# Battery_Monitoring_V2.net
KiCad netlist of a schematic drawn in EAGLE
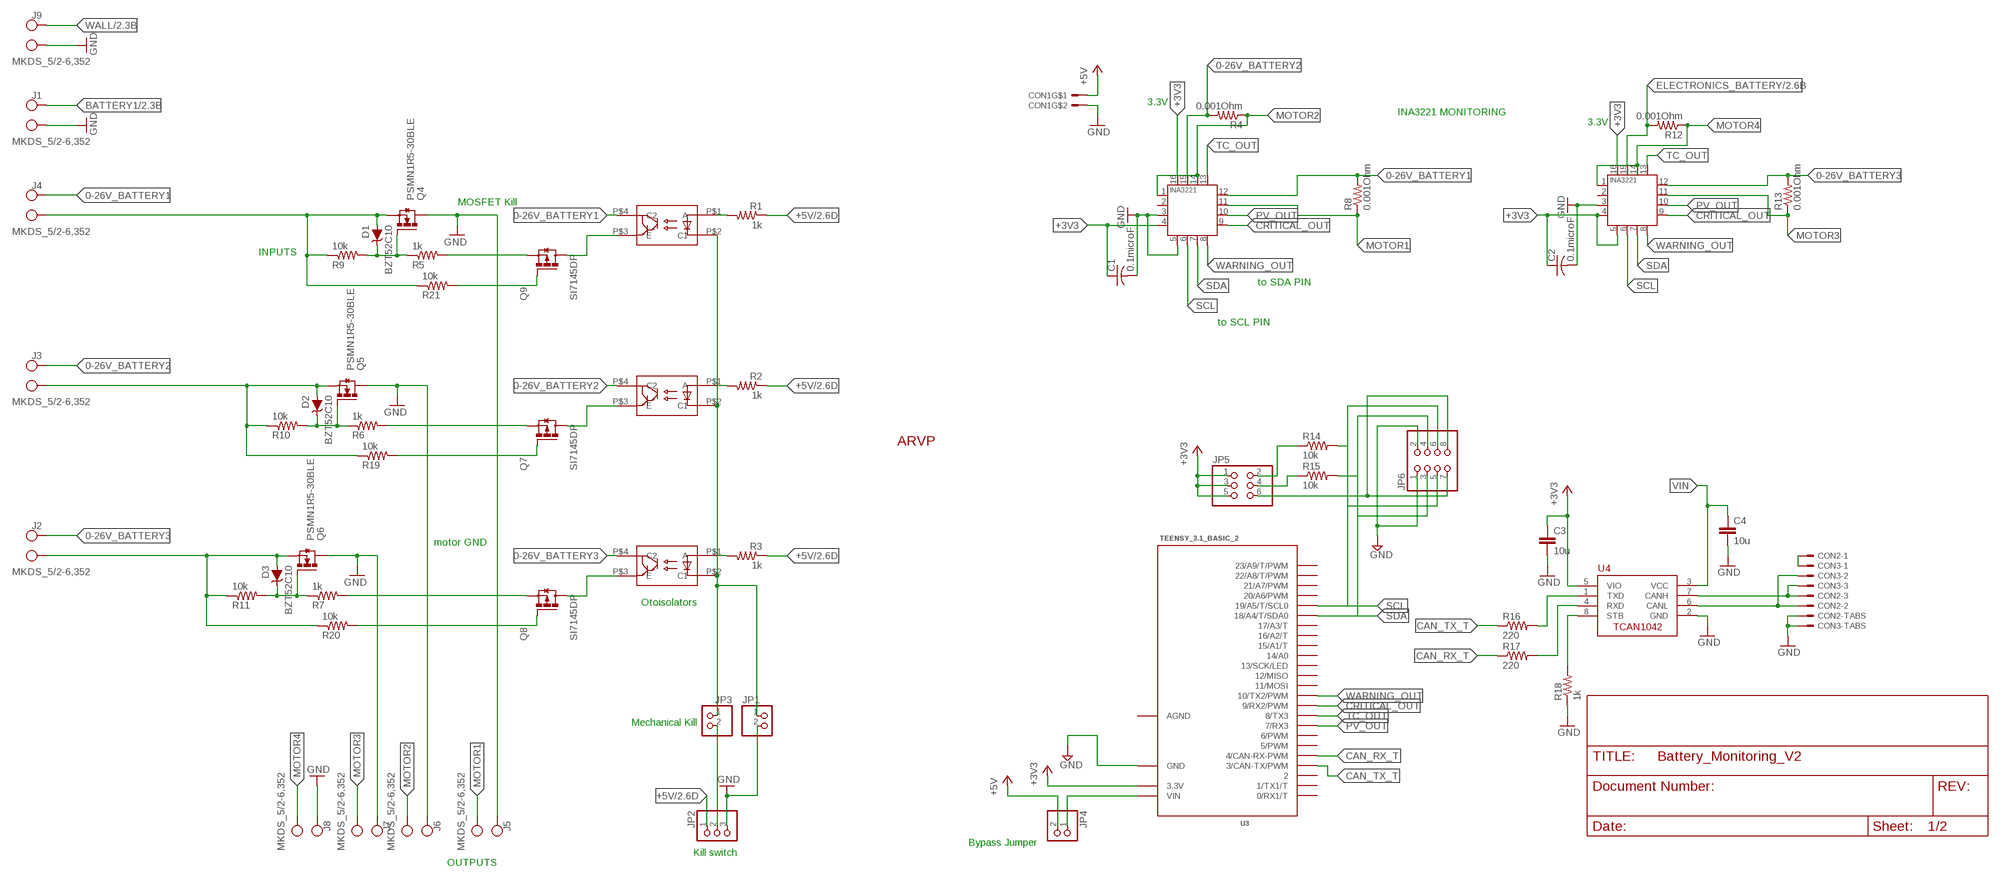
[diagram p0: schematic, sheet 1]
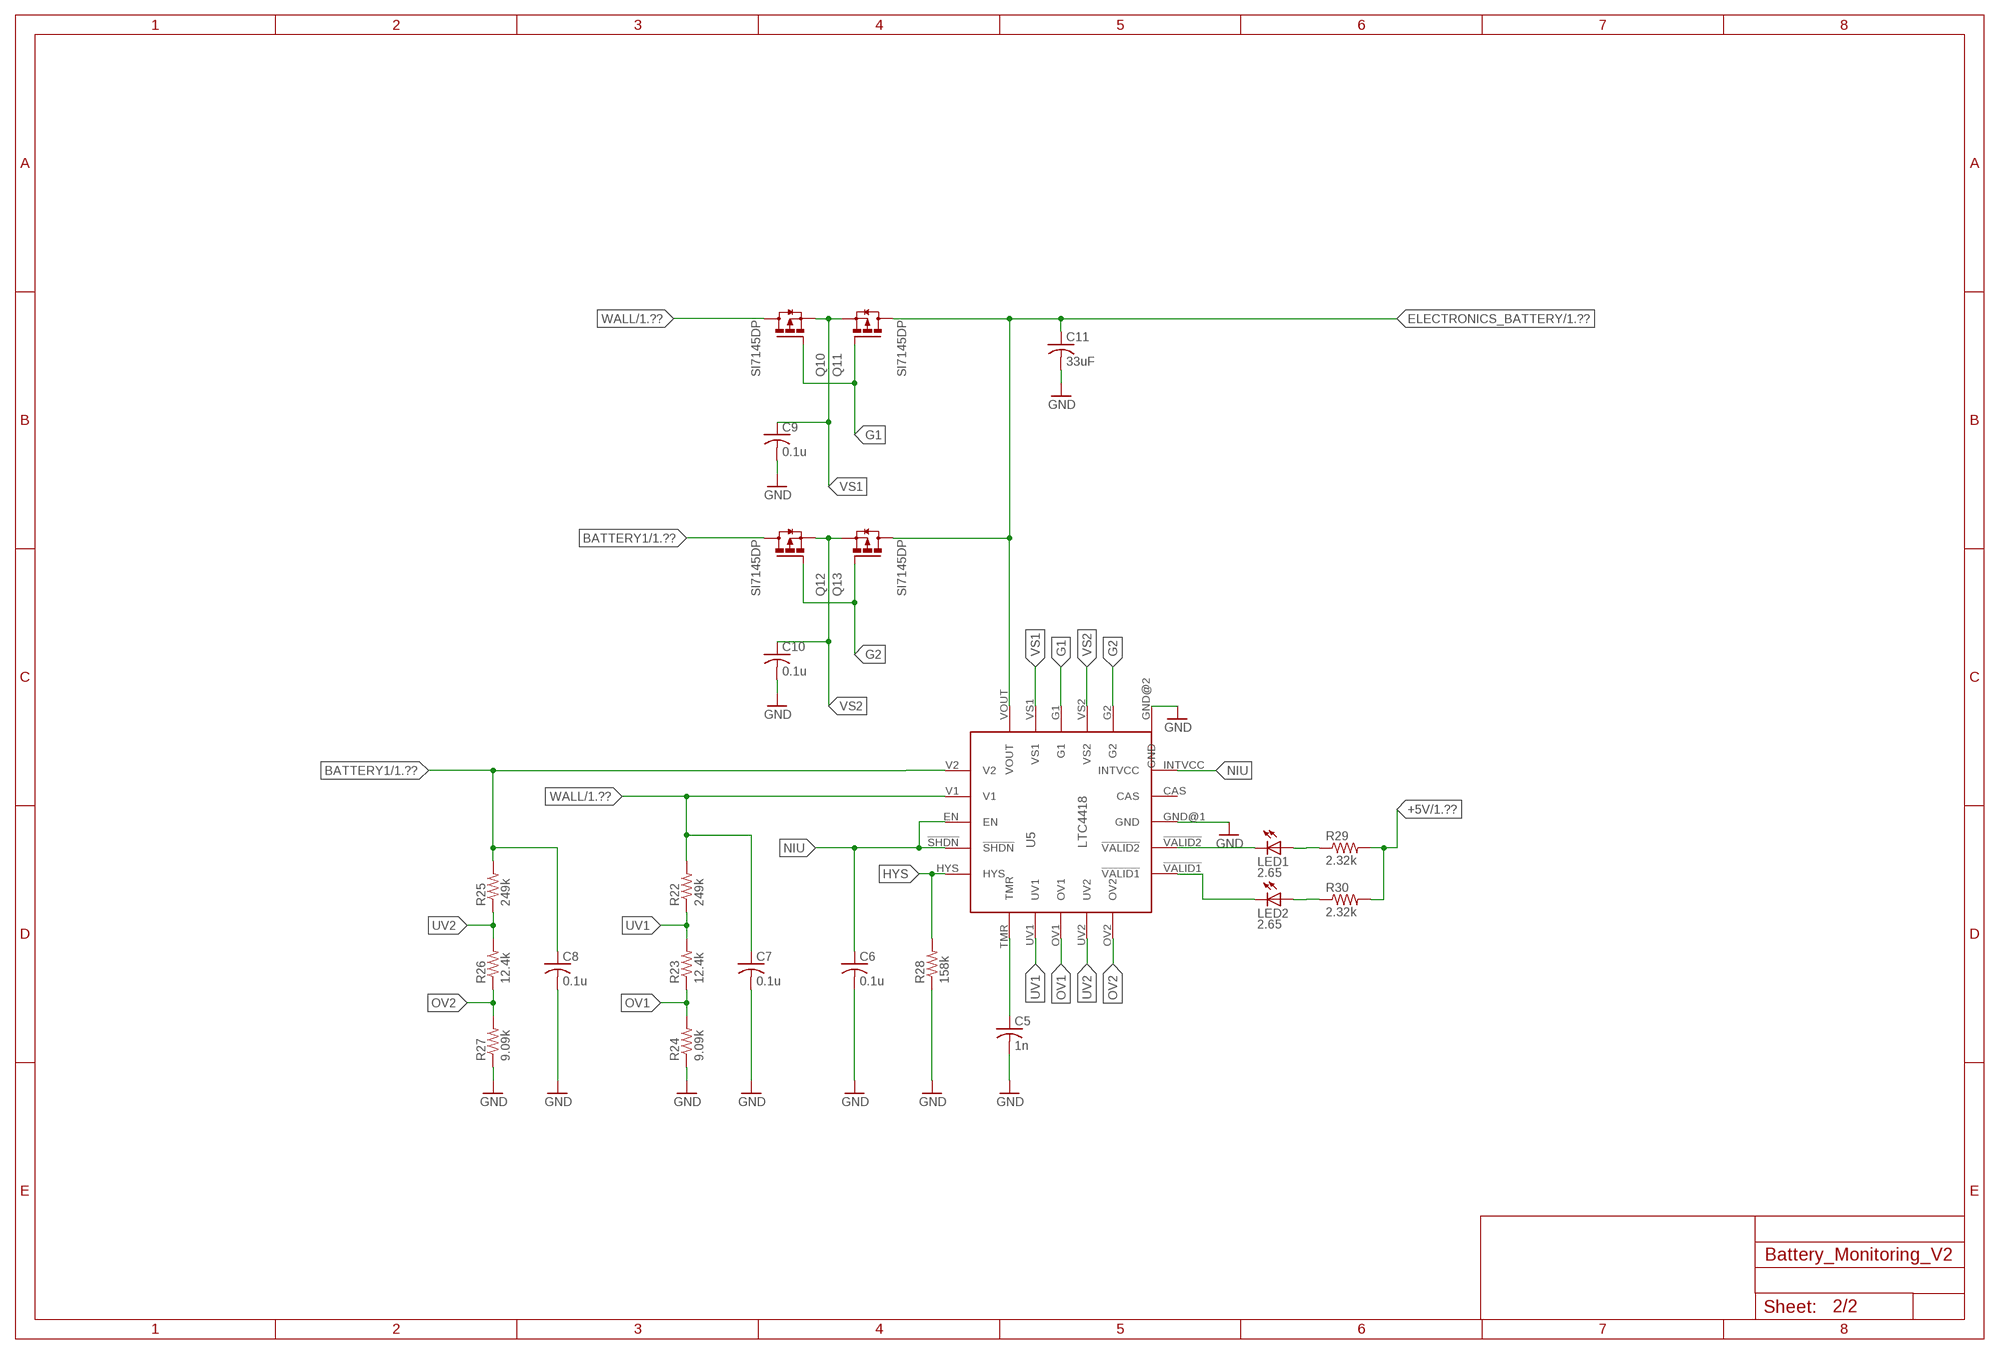
[diagram p1: schematic, sheet 2]

(export (version "E")
  (design (tool "Eeschema 10.0.6"))
  (components
    (comp (ref "ARVP1")
      (value "ARVP_LOGO")
      (footprint "eagle-import:ARVP")
      (libsource (lib "eagle-import") (part "ARVP_LOGO"))
    )
    (comp (ref "C1")
      (value "0.1microF")
      (footprint "eagle-import:C2012")
      (libsource (lib "eagle-import") (part "resistor_348_C-USC2012"))
    )
    (comp (ref "C2")
      (value "0.1microF")
      (footprint "eagle-import:C2012")
      (libsource (lib "eagle-import") (part "resistor_348_C-USC2012"))
    )
    (comp (ref "C3")
      (value "10u")
      (footprint "eagle-import:C0805")
      (libsource (lib "eagle-import") (part "C-EUC0805"))
    )
    (comp (ref "C4")
      (value "10u")
      (footprint "eagle-import:C0805")
      (libsource (lib "eagle-import") (part "C-EUC0805"))
    )
    (comp (ref "CON1")
      (value "MOLEX_5566-2")
      (footprint "eagle-import:5566-2")
      (libsource (lib "eagle-import") (part "MOLEX_5566-2"))
    )
    (comp (ref "CON2")
      (value "SM03B-GHS-TB")
      (footprint "eagle-import:SM03B-GHS-TB")
      (libsource (lib "eagle-import") (part "SM03B-GHS-TB"))
    )
    (comp (ref "CON3")
      (value "SM03B-GHS-TB")
      (footprint "eagle-import:SM03B-GHS-TB")
      (libsource (lib "eagle-import") (part "SM03B-GHS-TB"))
    )
    (comp (ref "D1")
      (value "BZT52C10")
      (footprint "eagle-import:SOD-123")
      (libsource (lib "eagle-import") (part "BZT52C10"))
    )
    (comp (ref "D2")
      (value "BZT52C10")
      (footprint "eagle-import:SOD-123")
      (libsource (lib "eagle-import") (part "BZT52C10"))
    )
    (comp (ref "D3")
      (value "BZT52C10")
      (footprint "eagle-import:SOD-123")
      (libsource (lib "eagle-import") (part "BZT52C10"))
    )
    (comp (ref "J1")
      (value "MKDS_5/2-6,352")
      (footprint "eagle-import:MKDS_5_2-6,35")
      (libsource (lib "eagle-import") (part "MKDS_5/2-6,352"))
    )
    (comp (ref "J2")
      (value "MKDS_5/2-6,352")
      (footprint "eagle-import:MKDS_5_2-6,35")
      (libsource (lib "eagle-import") (part "MKDS_5/2-6,352"))
    )
    (comp (ref "J3")
      (value "MKDS_5/2-6,352")
      (footprint "eagle-import:MKDS_5_2-6,35")
      (libsource (lib "eagle-import") (part "MKDS_5/2-6,352"))
    )
    (comp (ref "J4")
      (value "MKDS_5/2-6,352")
      (footprint "eagle-import:MKDS_5_2-6,35")
      (libsource (lib "eagle-import") (part "MKDS_5/2-6,352"))
    )
    (comp (ref "J5")
      (value "MKDS_5/2-6,352")
      (footprint "eagle-import:MKDS_5_2-6,35")
      (libsource (lib "eagle-import") (part "MKDS_5/2-6,352"))
    )
    (comp (ref "J6")
      (value "MKDS_5/2-6,352")
      (footprint "eagle-import:MKDS_5_2-6,35")
      (libsource (lib "eagle-import") (part "MKDS_5/2-6,352"))
    )
    (comp (ref "J7")
      (value "MKDS_5/2-6,352")
      (footprint "eagle-import:MKDS_5_2-6,35")
      (libsource (lib "eagle-import") (part "MKDS_5/2-6,352"))
    )
    (comp (ref "J8")
      (value "MKDS_5/2-6,352")
      (footprint "eagle-import:MKDS_5_2-6,35")
      (libsource (lib "eagle-import") (part "MKDS_5/2-6,352"))
    )
    (comp (ref "J9")
      (value "MKDS_5/2-6,352")
      (footprint "eagle-import:MKDS_5_2-6,35")
      (libsource (lib "eagle-import") (part "MKDS_5/2-6,352"))
    )
    (comp (ref "JP1")
      (value "PINHD-1X2")
      (footprint "eagle-import:1X02")
      (libsource (lib "eagle-import") (part "PINHD-1X2"))
    )
    (comp (ref "JP2")
      (value "PINHD-1X3")
      (footprint "eagle-import:1X03")
      (libsource (lib "eagle-import") (part "PINHD-1X3"))
    )
    (comp (ref "JP3")
      (value "PINHD-1X2")
      (footprint "eagle-import:1X02")
      (libsource (lib "eagle-import") (part "PINHD-1X2"))
    )
    (comp (ref "JP4")
      (value "PINHD-1X2")
      (footprint "eagle-import:1X02")
      (libsource (lib "eagle-import") (part "PINHD-1X2"))
    )
    (comp (ref "JP5")
      (value "PINHD-2X3")
      (footprint "eagle-import:2X03")
      (libsource (lib "eagle-import") (part "PINHD-2X3"))
    )
    (comp (ref "JP6")
      (value "PINHD-2X4")
      (footprint "eagle-import:2X04")
      (libsource (lib "eagle-import") (part "PINHD-2X4"))
    )
    (comp (ref "Q1")
      (value "TCLD1000CT")
      (footprint "eagle-import:SOP-4L")
      (fields (field (name "SPICEPREFIX") "E"))
      (libsource (lib "eagle-import") (part "TCLD1000CT"))
    )
    (comp (ref "Q2")
      (value "TCLD1000CT")
      (footprint "eagle-import:SOP-4L")
      (libsource (lib "eagle-import") (part "TCLD1000CT"))
    )
    (comp (ref "Q3")
      (value "TCLD1000CT")
      (footprint "eagle-import:SOP-4L")
      (libsource (lib "eagle-import") (part "TCLD1000CT"))
    )
    (comp (ref "Q4")
      (value "PSMN1R5-30BLE")
      (footprint "eagle-import:SOT404_D2PAK")
      (libsource (lib "eagle-import") (part "PSMN1R5-30BLE"))
    )
    (comp (ref "Q5")
      (value "PSMN1R5-30BLE")
      (footprint "eagle-import:SOT404_D2PAK")
      (libsource (lib "eagle-import") (part "PSMN1R5-30BLE"))
    )
    (comp (ref "Q6")
      (value "PSMN1R5-30BLE")
      (footprint "eagle-import:SOT404_D2PAK")
      (libsource (lib "eagle-import") (part "PSMN1R5-30BLE"))
    )
    (comp (ref "Q7")
      (value "SI7145DP")
      (footprint "eagle-import:SO-8_PPAK_TEST")
      (fields (field (name "MPN") "SI7145DP-T1-GE3"))
      (libsource (lib "eagle-import") (part "Si7145DP_SI7145DP"))
    )
    (comp (ref "Q8")
      (value "SI7145DP")
      (footprint "eagle-import:SO-8_PPAK_TEST")
      (fields (field (name "MPN") "SI7145DP-T1-GE3"))
      (libsource (lib "eagle-import") (part "Si7145DP_SI7145DP"))
    )
    (comp (ref "Q9")
      (value "SI7145DP")
      (footprint "eagle-import:SO-8_PPAK_TEST")
      (fields (field (name "MPN") "SI7145DP-T1-GE3"))
      (libsource (lib "eagle-import") (part "Si7145DP_SI7145DP"))
    )
    (comp (ref "R1")
      (value "1k")
      (footprint "eagle-import:R0805")
      (libsource (lib "eagle-import") (part "adafruit_420_R-US_R0805"))
    )
    (comp (ref "R2")
      (value "1k")
      (footprint "eagle-import:R0805")
      (libsource (lib "eagle-import") (part "adafruit_420_R-US_R0805"))
    )
    (comp (ref "R3")
      (value "1k")
      (footprint "eagle-import:R0805")
      (libsource (lib "eagle-import") (part "adafruit_420_R-US_R0805"))
    )
    (comp (ref "R4")
      (value "0.001Ohm")
      (footprint "eagle-import:3920")
      (libsource (lib "eagle-import") (part "HCS3920FT1L00"))
    )
    (comp (ref "R5")
      (value "1k")
      (footprint "eagle-import:M1206")
      (libsource (lib "eagle-import") (part "adafruit_420_R-US_M1206"))
    )
    (comp (ref "R6")
      (value "1k")
      (footprint "eagle-import:M1206")
      (libsource (lib "eagle-import") (part "adafruit_420_R-US_M1206"))
    )
    (comp (ref "R7")
      (value "1k")
      (footprint "eagle-import:M1206")
      (libsource (lib "eagle-import") (part "adafruit_420_R-US_M1206"))
    )
    (comp (ref "R8")
      (value "0.001Ohm")
      (footprint "eagle-import:3920")
      (libsource (lib "eagle-import") (part "HCS3920FT1L00"))
    )
    (comp (ref "R9")
      (value "10k")
      (footprint "eagle-import:M1206")
      (libsource (lib "eagle-import") (part "adafruit_420_R-US_M1206"))
    )
    (comp (ref "R10")
      (value "10k")
      (footprint "eagle-import:M1206")
      (libsource (lib "eagle-import") (part "adafruit_420_R-US_M1206"))
    )
    (comp (ref "R11")
      (value "10k")
      (footprint "eagle-import:M1206")
      (libsource (lib "eagle-import") (part "adafruit_420_R-US_M1206"))
    )
    (comp (ref "R12")
      (value "0.001Ohm")
      (footprint "eagle-import:3920")
      (libsource (lib "eagle-import") (part "HCS3920FT1L00"))
    )
    (comp (ref "R13")
      (value "0.001Ohm")
      (footprint "eagle-import:3920")
      (libsource (lib "eagle-import") (part "HCS3920FT1L00"))
    )
    (comp (ref "R14")
      (value "10k")
      (footprint "eagle-import:R1206")
      (libsource (lib "eagle-import") (part "rcl_334_R-US_R1206"))
    )
    (comp (ref "R15")
      (value "10k")
      (footprint "eagle-import:R1206")
      (libsource (lib "eagle-import") (part "rcl_334_R-US_R1206"))
    )
    (comp (ref "R16")
      (value "220")
      (footprint "eagle-import:R0805")
      (libsource (lib "eagle-import") (part "rcl_334_R-US_R0805"))
    )
    (comp (ref "R17")
      (value "220")
      (footprint "eagle-import:R0805")
      (libsource (lib "eagle-import") (part "rcl_334_R-US_R0805"))
    )
    (comp (ref "R18")
      (value "1k")
      (footprint "eagle-import:R0805")
      (libsource (lib "eagle-import") (part "rcl_334_R-US_R0805"))
    )
    (comp (ref "R19")
      (value "10k")
      (footprint "eagle-import:M1206")
      (fields (field (name "MPN") "RC0603FR-0710KL"))
      (libsource (lib "eagle-import") (part "R-US_M1206"))
    )
    (comp (ref "R20")
      (value "10k")
      (footprint "eagle-import:M1206")
      (fields (field (name "MPN") "RC0603FR-0710KL"))
      (libsource (lib "eagle-import") (part "R-US_M1206"))
    )
    (comp (ref "R21")
      (value "10k")
      (footprint "eagle-import:M1206")
      (fields (field (name "MPN") "RC0603FR-0710KL"))
      (libsource (lib "eagle-import") (part "adafruit_420_R-US_M1206"))
    )
    (comp (ref "U1")
      (value "INA3221.")
      (footprint "eagle-import:HVQFN16_4X4")
      (libsource (lib "eagle-import") (part "INA3221."))
    )
    (comp (ref "U2")
      (value "INA3221.")
      (footprint "eagle-import:HVQFN16_4X4")
      (libsource (lib "eagle-import") (part "INA3221."))
    )
    (comp (ref "U3")
      (value "TEENSY_3.1_BASIC_2")
      (footprint "eagle-import:TEENSY_3.1_BASIC_2")
      (libsource (lib "eagle-import") (part "TEENSY_3.1_BASIC_2"))
    )
    (comp (ref "U4")
      (value "TCAN1042HVDR")
      (footprint "eagle-import:SO-8")
      (libsource (lib "eagle-import") (part "TCAN1042HVDR"))
    )
    (comp (ref "C5")
      (value "1n")
      (footprint "eagle-import:C0805")
      (libsource (lib "eagle-import") (part "C-USC0805"))
    )
    (comp (ref "C6")
      (value "0.1u")
      (footprint "eagle-import:C0805")
      (libsource (lib "eagle-import") (part "C-USC0805"))
    )
    (comp (ref "C7")
      (value "0.1u")
      (footprint "eagle-import:C0805")
      (libsource (lib "eagle-import") (part "C-USC0805"))
    )
    (comp (ref "C8")
      (value "0.1u")
      (footprint "eagle-import:C0805")
      (libsource (lib "eagle-import") (part "C-USC0805"))
    )
    (comp (ref "C9")
      (value "0.1u")
      (footprint "eagle-import:C0805")
      (libsource (lib "eagle-import") (part "C-USC0805"))
    )
    (comp (ref "C10")
      (value "0.1u")
      (footprint "eagle-import:C0805")
      (libsource (lib "eagle-import") (part "C-USC0805"))
    )
    (comp (ref "C11")
      (value "33uF")
      (footprint "eagle-import:C1206")
      (libsource (lib "eagle-import") (part "C-USC1206"))
    )
    (comp (ref "LED1")
      (value "2.65")
      (footprint "eagle-import:SML0805")
      (libsource (lib "eagle-import") (part "LEDSML0805"))
    )
    (comp (ref "LED2")
      (value "2.65")
      (footprint "eagle-import:SML0805")
      (libsource (lib "eagle-import") (part "LEDSML0805"))
    )
    (comp (ref "Q10")
      (value "SI7145DP")
      (footprint "eagle-import:SO-8_PPAK_TEST")
      (libsource (lib "eagle-import") (part "SI7145DP"))
    )
    (comp (ref "Q11")
      (value "SI7145DP")
      (footprint "eagle-import:SO-8_PPAK_TEST")
      (libsource (lib "eagle-import") (part "SI7145DP"))
    )
    (comp (ref "Q12")
      (value "SI7145DP")
      (footprint "eagle-import:SO-8_PPAK_TEST")
      (libsource (lib "eagle-import") (part "SI7145DP"))
    )
    (comp (ref "Q13")
      (value "SI7145DP")
      (footprint "eagle-import:SO-8_PPAK_TEST")
      (libsource (lib "eagle-import") (part "SI7145DP"))
    )
    (comp (ref "R22")
      (value "249k")
      (footprint "eagle-import:R1206")
      (libsource (lib "eagle-import") (part "adafruit_420_R-US_R1206"))
    )
    (comp (ref "R23")
      (value "12.4k")
      (footprint "eagle-import:R0805")
      (libsource (lib "eagle-import") (part "adafruit_420_R-US_R0805"))
    )
    (comp (ref "R24")
      (value "9.09k")
      (footprint "eagle-import:R0805")
      (libsource (lib "eagle-import") (part "adafruit_420_R-US_R0805"))
    )
    (comp (ref "R25")
      (value "249k")
      (footprint "eagle-import:R1206")
      (libsource (lib "eagle-import") (part "adafruit_420_R-US_R1206"))
    )
    (comp (ref "R26")
      (value "12.4k")
      (footprint "eagle-import:R0805")
      (libsource (lib "eagle-import") (part "adafruit_420_R-US_R0805"))
    )
    (comp (ref "R27")
      (value "9.09k")
      (footprint "eagle-import:R0805")
      (libsource (lib "eagle-import") (part "adafruit_420_R-US_R0805"))
    )
    (comp (ref "R28")
      (value "158k")
      (footprint "eagle-import:R0805")
      (libsource (lib "eagle-import") (part "adafruit_420_R-US_R0805"))
    )
    (comp (ref "R29")
      (value "2.32k")
      (footprint "eagle-import:R0805")
      (libsource (lib "eagle-import") (part "adafruit_420_R-US_R0805"))
    )
    (comp (ref "R30")
      (value "2.32k")
      (footprint "eagle-import:R0805")
      (libsource (lib "eagle-import") (part "adafruit_420_R-US_R0805"))
    )
    (comp (ref "U5")
      (value "LTC4418")
      (footprint "eagle-import:20-QFN(4X4)")
      (libsource (lib "eagle-import") (part "LTC4418"))
    )
  )
  (nets
    (net (code "1") (name "+3V3") (class "Default")
      (node (ref "C1") (pin "1") (pinfunction "1_1") (pintype "passive"))
      (node (ref "C2") (pin "1") (pinfunction "1_1") (pintype "passive"))
      (node (ref "C3") (pin "1") (pinfunction "1_1") (pintype "passive"))
      (node (ref "JP5") (pin "1") (pinfunction "1_1") (pintype "passive"))
      (node (ref "JP5") (pin "3") (pinfunction "3_3") (pintype "passive"))
      (node (ref "JP5") (pin "5") (pinfunction "5_5") (pintype "passive"))
      (node (ref "U1") (pin "16") (pinfunction "VPU_16") (pintype "input"))
      (node (ref "U1") (pin "4") (pinfunction "VS_4") (pintype "power_in"))
      (node (ref "U2") (pin "16") (pinfunction "VPU_16") (pintype "input"))
      (node (ref "U2") (pin "4") (pinfunction "VS_4") (pintype "power_in"))
      (node (ref "U2") (pin "5") (pinfunction "A0_5") (pintype "input"))
      (node (ref "U3") (pin "3.3V") (pinfunction "3.3V_3.3V") (pintype "power_in"))
      (node (ref "U4") (pin "5") (pinfunction "VIO_5") (pintype "bidirectional"))
    )
    (net (code "2") (name "+5V") (class "Default")
      (node (ref "CON1") (pin "1") (pinfunction "S_1") (pintype "passive"))
      (node (ref "JP2") (pin "1") (pinfunction "1_1") (pintype "passive"))
      (node (ref "JP4") (pin "2") (pinfunction "2_2") (pintype "passive"))
      (node (ref "R1") (pin "1") (pinfunction "1_1") (pintype "passive"))
      (node (ref "R2") (pin "1") (pinfunction "1_1") (pintype "passive"))
      (node (ref "R29") (pin "2") (pinfunction "2_2") (pintype "passive"))
      (node (ref "R3") (pin "1") (pinfunction "1_1") (pintype "passive"))
      (node (ref "R30") (pin "2") (pinfunction "2_2") (pintype "passive"))
    )
    (net (code "3") (name "0-26V_BATTERY1") (class "Default")
      (node (ref "J4") (pin "2") (pinfunction "KL1_2") (pintype "passive"))
      (node (ref "Q1") (pin "P$4") (pinfunction "C2_P$4") (pintype "bidirectional"))
      (node (ref "R8") (pin "P$2") (pinfunction "2_P$2") (pintype "passive"))
      (node (ref "U1") (pin "12") (pinfunction "IN+1_12") (pintype "input"))
    )
    (net (code "4") (name "0-26V_BATTERY2") (class "Default")
      (node (ref "J3") (pin "2") (pinfunction "KL1_2") (pintype "passive"))
      (node (ref "Q2") (pin "P$4") (pinfunction "C2_P$4") (pintype "bidirectional"))
      (node (ref "R4") (pin "P$2") (pinfunction "2_P$2") (pintype "passive"))
      (node (ref "U1") (pin "15") (pinfunction "IN+2_15") (pintype "input"))
    )
    (net (code "5") (name "0-26V_BATTERY3") (class "Default")
      (node (ref "J2") (pin "2") (pinfunction "KL1_2") (pintype "passive"))
      (node (ref "Q3") (pin "P$4") (pinfunction "C2_P$4") (pintype "bidirectional"))
      (node (ref "R13") (pin "P$2") (pinfunction "2_P$2") (pintype "passive"))
      (node (ref "U2") (pin "12") (pinfunction "IN+1_12") (pintype "input"))
    )
    (net (code "6") (name "AGND") (class "Default")
      (node (ref "U3") (pin "AGND") (pinfunction "AGND_AGND") (pintype "power_in"))
    )
    (net (code "7") (name "BATTERY1") (class "Default")
      (node (ref "C8") (pin "1") (pinfunction "1_1") (pintype "passive"))
      (node (ref "J1") (pin "2") (pinfunction "KL1_2") (pintype "passive"))
      (node (ref "Q12") (pin "D@1") (pinfunction "D_D@1") (pintype "passive"))
      (node (ref "Q12") (pin "D@2") (pinfunction "D_D@2") (pintype "passive"))
      (node (ref "Q12") (pin "D@3") (pinfunction "D_D@3") (pintype "passive"))
      (node (ref "Q12") (pin "D@4") (pinfunction "D_D@4") (pintype "passive"))
      (node (ref "Q12") (pin "D@5") (pinfunction "D_D@5") (pintype "passive"))
      (node (ref "R25") (pin "2") (pinfunction "2_2") (pintype "passive"))
      (node (ref "U5") (pin "V2") (pinfunction "V2_V2") (pintype "bidirectional"))
    )
    (net (code "8") (name "CAN_RX_T") (class "Default")
      (node (ref "R17") (pin "1") (pinfunction "1_1") (pintype "passive"))
      (node (ref "U3") (pin "4") (pinfunction "4/CAN-RX-PWM_4") (pintype "bidirectional"))
    )
    (net (code "9") (name "CAN_TX_T") (class "Default")
      (node (ref "R16") (pin "1") (pinfunction "1_1") (pintype "passive"))
      (node (ref "U3") (pin "3") (pinfunction "3/CAN-TX/PWM_3") (pintype "bidirectional"))
    )
    (net (code "10") (name "CRITICAL_OUT") (class "Default")
      (node (ref "U1") (pin "9") (pinfunction "CRITICAL_9") (pintype "output"))
      (node (ref "U2") (pin "9") (pinfunction "CRITICAL_9") (pintype "output"))
      (node (ref "U3") (pin "9") (pinfunction "9/RX2/PWM_9") (pintype "bidirectional"))
    )
    (net (code "11") (name "ELECTRONICS_BATTERY") (class "Default")
      (node (ref "C11") (pin "1") (pinfunction "1_1") (pintype "passive"))
      (node (ref "Q11") (pin "D@1") (pinfunction "D_D@1") (pintype "passive"))
      (node (ref "Q11") (pin "D@2") (pinfunction "D_D@2") (pintype "passive"))
      (node (ref "Q11") (pin "D@3") (pinfunction "D_D@3") (pintype "passive"))
      (node (ref "Q11") (pin "D@4") (pinfunction "D_D@4") (pintype "passive"))
      (node (ref "Q11") (pin "D@5") (pinfunction "D_D@5") (pintype "passive"))
      (node (ref "Q13") (pin "D@1") (pinfunction "D_D@1") (pintype "passive"))
      (node (ref "Q13") (pin "D@2") (pinfunction "D_D@2") (pintype "passive"))
      (node (ref "Q13") (pin "D@3") (pinfunction "D_D@3") (pintype "passive"))
      (node (ref "Q13") (pin "D@4") (pinfunction "D_D@4") (pintype "passive"))
      (node (ref "Q13") (pin "D@5") (pinfunction "D_D@5") (pintype "passive"))
      (node (ref "R12") (pin "P$2") (pinfunction "2_P$2") (pintype "passive"))
      (node (ref "U2") (pin "15") (pinfunction "IN+2_15") (pintype "input"))
      (node (ref "U5") (pin "VOUT") (pinfunction "VOUT_VOUT") (pintype "power_in"))
    )
    (net (code "12") (name "G1") (class "Default")
      (node (ref "Q10") (pin "G") (pinfunction "G_G") (pintype "passive"))
      (node (ref "Q11") (pin "G") (pinfunction "G_G") (pintype "passive"))
      (node (ref "U5") (pin "G1") (pinfunction "G1_G1") (pintype "bidirectional"))
    )
    (net (code "13") (name "G2") (class "Default")
      (node (ref "Q12") (pin "G") (pinfunction "G_G") (pintype "passive"))
      (node (ref "Q13") (pin "G") (pinfunction "G_G") (pintype "passive"))
      (node (ref "U5") (pin "G2") (pinfunction "G2_G2") (pintype "bidirectional"))
    )
    (net (code "14") (name "GND") (class "Default")
      (node (ref "C1") (pin "2") (pinfunction "2_2") (pintype "passive"))
      (node (ref "C10") (pin "2") (pinfunction "2_2") (pintype "passive"))
      (node (ref "C11") (pin "2") (pinfunction "2_2") (pintype "passive"))
      (node (ref "C2") (pin "2") (pinfunction "2_2") (pintype "passive"))
      (node (ref "C3") (pin "2") (pinfunction "2_2") (pintype "passive"))
      (node (ref "C4") (pin "2") (pinfunction "2_2") (pintype "passive"))
      (node (ref "C5") (pin "2") (pinfunction "2_2") (pintype "passive"))
      (node (ref "C6") (pin "2") (pinfunction "2_2") (pintype "passive"))
      (node (ref "C7") (pin "2") (pinfunction "2_2") (pintype "passive"))
      (node (ref "C8") (pin "2") (pinfunction "2_2") (pintype "passive"))
      (node (ref "C9") (pin "2") (pinfunction "2_2") (pintype "passive"))
      (node (ref "CON1") (pin "2") (pinfunction "S_2") (pintype "passive"))
      (node (ref "CON2") (pin "P$4") (pinfunction "S_P$4") (pintype "passive"))
      (node (ref "CON2") (pin "P$5") (pinfunction "S_P$5") (pintype "passive"))
      (node (ref "CON3") (pin "P$4") (pinfunction "S_P$4") (pintype "passive"))
      (node (ref "CON3") (pin "P$5") (pinfunction "S_P$5") (pintype "passive"))
      (node (ref "J1") (pin "1") (pinfunction "KL_1") (pintype "passive"))
      (node (ref "J5") (pin "2") (pinfunction "KL1_2") (pintype "passive"))
      (node (ref "J6") (pin "2") (pinfunction "KL1_2") (pintype "passive"))
      (node (ref "J7") (pin "2") (pinfunction "KL1_2") (pintype "passive"))
      (node (ref "J8") (pin "2") (pinfunction "KL1_2") (pintype "passive"))
      (node (ref "J9") (pin "1") (pinfunction "KL_1") (pintype "passive"))
      (node (ref "JP1") (pin "2") (pinfunction "2_2") (pintype "passive"))
      (node (ref "JP2") (pin "3") (pinfunction "3_3") (pintype "passive"))
      (node (ref "JP6") (pin "1") (pinfunction "1_1") (pintype "passive"))
      (node (ref "JP6") (pin "2") (pinfunction "2_2") (pintype "passive"))
      (node (ref "Q4") (pin "2D") (pinfunction "D_2D") (pintype "passive"))
      (node (ref "Q5") (pin "2D") (pinfunction "D_2D") (pintype "passive"))
      (node (ref "Q6") (pin "2D") (pinfunction "D_2D") (pintype "passive"))
      (node (ref "R18") (pin "1") (pinfunction "1_1") (pintype "passive"))
      (node (ref "R24") (pin "1") (pinfunction "1_1") (pintype "passive"))
      (node (ref "R27") (pin "1") (pinfunction "1_1") (pintype "passive"))
      (node (ref "R28") (pin "1") (pinfunction "1_1") (pintype "passive"))
      (node (ref "U1") (pin "3") (pinfunction "GND_3") (pintype "power_in"))
      (node (ref "U1") (pin "5") (pinfunction "A0_5") (pintype "input"))
      (node (ref "U2") (pin "3") (pinfunction "GND_3") (pintype "power_in"))
      (node (ref "U3") (pin "GND") (pinfunction "GND_GND") (pintype "power_in"))
      (node (ref "U4") (pin "2") (pinfunction "GND_2") (pintype "bidirectional"))
      (node (ref "U5") (pin "GND@1") (pinfunction "GND_GND@1") (pintype "power_in"))
      (node (ref "U5") (pin "GND@2") (pinfunction "GND_GND@2") (pintype "power_in"))
    )
    (net (code "15") (name "HYS") (class "Default")
      (node (ref "R28") (pin "2") (pinfunction "2_2") (pintype "passive"))
      (node (ref "U5") (pin "HYS") (pinfunction "HYS_HYS") (pintype "bidirectional"))
    )
    (net (code "16") (name "MOTOR1") (class "Default")
      (node (ref "J5") (pin "1") (pinfunction "KL_1") (pintype "passive"))
      (node (ref "R8") (pin "P$1") (pinfunction "1_P$1") (pintype "passive"))
      (node (ref "U1") (pin "11") (pinfunction "IN-1_11") (pintype "input"))
    )
    (net (code "17") (name "MOTOR2") (class "Default")
      (node (ref "J6") (pin "1") (pinfunction "KL_1") (pintype "passive"))
      (node (ref "R4") (pin "P$1") (pinfunction "1_P$1") (pintype "passive"))
      (node (ref "U1") (pin "1") (pinfunction "IN-3_1") (pintype "input"))
      (node (ref "U1") (pin "14") (pinfunction "IN-2_14") (pintype "input"))
    )
    (net (code "18") (name "MOTOR3") (class "Default")
      (node (ref "J7") (pin "1") (pinfunction "KL_1") (pintype "passive"))
      (node (ref "R13") (pin "P$1") (pinfunction "1_P$1") (pintype "passive"))
      (node (ref "U2") (pin "11") (pinfunction "IN-1_11") (pintype "input"))
    )
    (net (code "19") (name "MOTOR4") (class "Default")
      (node (ref "J8") (pin "1") (pinfunction "KL_1") (pintype "passive"))
      (node (ref "R12") (pin "P$1") (pinfunction "1_P$1") (pintype "passive"))
      (node (ref "U2") (pin "1") (pinfunction "IN-3_1") (pintype "input"))
      (node (ref "U2") (pin "14") (pinfunction "IN-2_14") (pintype "input"))
    )
    (net (code "20") (name "NIU") (class "Default")
      (node (ref "C6") (pin "1") (pinfunction "1_1") (pintype "passive"))
      (node (ref "U5") (pin "!SHDN") (pinfunction "~{SHDN}_!SHDN") (pintype "bidirectional"))
      (node (ref "U5") (pin "EN") (pinfunction "EN_EN") (pintype "bidirectional"))
      (node (ref "U5") (pin "INTVCC") (pinfunction "INTVCC_INTVCC") (pintype "bidirectional"))
    )
    (net (code "21") (name "Net-(C5-Pad1)") (class "Default")
      (node (ref "C5") (pin "1") (pinfunction "1_1") (pintype "passive"))
      (node (ref "U5") (pin "TMR") (pinfunction "TMR_TMR") (pintype "bidirectional"))
    )
    (net (code "22") (name "Net-(CON2A-S)") (class "Default")
      (node (ref "CON2") (pin "P$1") (pinfunction "S_P$1") (pintype "passive"))
      (node (ref "CON3") (pin "P$1") (pinfunction "S_P$1") (pintype "passive"))
    )
    (net (code "23") (name "Net-(CON2B-S)") (class "Default")
      (node (ref "CON2") (pin "P$2") (pinfunction "S_P$2") (pintype "passive"))
      (node (ref "CON3") (pin "P$2") (pinfunction "S_P$2") (pintype "passive"))
      (node (ref "U4") (pin "6") (pinfunction "CANL_6") (pintype "bidirectional"))
    )
    (net (code "24") (name "Net-(CON2C-S)") (class "Default")
      (node (ref "CON2") (pin "P$3") (pinfunction "S_P$3") (pintype "passive"))
      (node (ref "CON3") (pin "P$3") (pinfunction "S_P$3") (pintype "passive"))
      (node (ref "U4") (pin "7") (pinfunction "CANH_7") (pintype "bidirectional"))
    )
    (net (code "25") (name "Net-(D1-A)") (class "Default")
      (node (ref "D1") (pin "P$2") (pinfunction "A_P$2") (pintype "passive"))
      (node (ref "J4") (pin "1") (pinfunction "KL_1") (pintype "passive"))
      (node (ref "Q4") (pin "3S") (pinfunction "S_3S") (pintype "passive"))
      (node (ref "R21") (pin "1") (pinfunction "1_1") (pintype "passive"))
      (node (ref "R9") (pin "1") (pinfunction "1_1") (pintype "passive"))
    )
    (net (code "26") (name "Net-(D1-C)") (class "Default")
      (node (ref "D1") (pin "P$1") (pinfunction "C_P$1") (pintype "passive"))
      (node (ref "Q4") (pin "1G") (pinfunction "G_1G") (pintype "passive"))
      (node (ref "R5") (pin "1") (pinfunction "1_1") (pintype "passive"))
      (node (ref "R9") (pin "2") (pinfunction "2_2") (pintype "passive"))
    )
    (net (code "27") (name "Net-(D2-A)") (class "Default")
      (node (ref "D2") (pin "P$2") (pinfunction "A_P$2") (pintype "passive"))
      (node (ref "J3") (pin "1") (pinfunction "KL_1") (pintype "passive"))
      (node (ref "Q5") (pin "3S") (pinfunction "S_3S") (pintype "passive"))
      (node (ref "R10") (pin "1") (pinfunction "1_1") (pintype "passive"))
      (node (ref "R19") (pin "1") (pinfunction "1_1") (pintype "passive"))
    )
    (net (code "28") (name "Net-(D2-C)") (class "Default")
      (node (ref "D2") (pin "P$1") (pinfunction "C_P$1") (pintype "passive"))
      (node (ref "Q5") (pin "1G") (pinfunction "G_1G") (pintype "passive"))
      (node (ref "R10") (pin "2") (pinfunction "2_2") (pintype "passive"))
      (node (ref "R6") (pin "1") (pinfunction "1_1") (pintype "passive"))
    )
    (net (code "29") (name "Net-(D3-A)") (class "Default")
      (node (ref "D3") (pin "P$2") (pinfunction "A_P$2") (pintype "passive"))
      (node (ref "J2") (pin "1") (pinfunction "KL_1") (pintype "passive"))
      (node (ref "Q6") (pin "3S") (pinfunction "S_3S") (pintype "passive"))
      (node (ref "R11") (pin "1") (pinfunction "1_1") (pintype "passive"))
      (node (ref "R20") (pin "1") (pinfunction "1_1") (pintype "passive"))
    )
    (net (code "30") (name "Net-(D3-C)") (class "Default")
      (node (ref "D3") (pin "P$1") (pinfunction "C_P$1") (pintype "passive"))
      (node (ref "Q6") (pin "1G") (pinfunction "G_1G") (pintype "passive"))
      (node (ref "R11") (pin "2") (pinfunction "2_2") (pintype "passive"))
      (node (ref "R7") (pin "1") (pinfunction "1_1") (pintype "passive"))
    )
    (net (code "31") (name "Net-(JP2-Pad2)") (class "Default")
      (node (ref "JP2") (pin "2") (pinfunction "2_2") (pintype "passive"))
      (node (ref "JP3") (pin "2") (pinfunction "2_2") (pintype "passive"))
    )
    (net (code "32") (name "Net-(JP5-Pad2)") (class "Default")
      (node (ref "JP5") (pin "2") (pinfunction "2_2") (pintype "passive"))
      (node (ref "R14") (pin "1") (pinfunction "1_1") (pintype "passive"))
    )
    (net (code "33") (name "Net-(JP5-Pad4)") (class "Default")
      (node (ref "JP5") (pin "4") (pinfunction "4_4") (pintype "passive"))
      (node (ref "R15") (pin "1") (pinfunction "1_1") (pintype "passive"))
    )
    (net (code "34") (name "Net-(JP5-Pad6)") (class "Default")
      (node (ref "JP5") (pin "6") (pinfunction "6_6") (pintype "passive"))
      (node (ref "JP6") (pin "7") (pinfunction "7_7") (pintype "passive"))
      (node (ref "JP6") (pin "8") (pinfunction "8_8") (pintype "passive"))
    )
    (net (code "35") (name "Net-(LED1-PadA)") (class "Default")
      (node (ref "LED1") (pin "A") (pinfunction "A_A") (pintype "passive"))
      (node (ref "R29") (pin "1") (pinfunction "1_1") (pintype "passive"))
    )
    (net (code "36") (name "Net-(LED2-PadA)") (class "Default")
      (node (ref "LED2") (pin "A") (pinfunction "A_A") (pintype "passive"))
      (node (ref "R30") (pin "1") (pinfunction "1_1") (pintype "passive"))
    )
    (net (code "37") (name "Net-(Q1-A)") (class "Default")
      (node (ref "Q1") (pin "P$1") (pinfunction "A_P$1") (pintype "bidirectional"))
      (node (ref "R1") (pin "2") (pinfunction "2_2") (pintype "passive"))
    )
    (net (code "38") (name "Net-(Q1-C1)") (class "Default")
      (node (ref "JP1") (pin "1") (pinfunction "1_1") (pintype "passive"))
      (node (ref "JP3") (pin "1") (pinfunction "1_1") (pintype "passive"))
      (node (ref "Q1") (pin "P$2") (pinfunction "C1_P$2") (pintype "bidirectional"))
      (node (ref "Q2") (pin "P$2") (pinfunction "C1_P$2") (pintype "bidirectional"))
      (node (ref "Q3") (pin "P$2") (pinfunction "C1_P$2") (pintype "bidirectional"))
    )
    (net (code "39") (name "Net-(Q1-E)") (class "Default")
      (node (ref "Q1") (pin "P$3") (pinfunction "E_P$3") (pintype "bidirectional"))
      (node (ref "Q9") (pin "D@1") (pinfunction "D_D@1") (pintype "passive"))
      (node (ref "Q9") (pin "D@2") (pinfunction "D_D@2") (pintype "passive"))
      (node (ref "Q9") (pin "D@3") (pinfunction "D_D@3") (pintype "passive"))
      (node (ref "Q9") (pin "D@4") (pinfunction "D_D@4") (pintype "passive"))
      (node (ref "Q9") (pin "D@5") (pinfunction "D_D@5") (pintype "passive"))
    )
    (net (code "40") (name "Net-(Q2-A)") (class "Default")
      (node (ref "Q2") (pin "P$1") (pinfunction "A_P$1") (pintype "bidirectional"))
      (node (ref "R2") (pin "2") (pinfunction "2_2") (pintype "passive"))
    )
    (net (code "41") (name "Net-(Q2-E)") (class "Default")
      (node (ref "Q2") (pin "P$3") (pinfunction "E_P$3") (pintype "bidirectional"))
      (node (ref "Q7") (pin "D@1") (pinfunction "D_D@1") (pintype "passive"))
      (node (ref "Q7") (pin "D@2") (pinfunction "D_D@2") (pintype "passive"))
      (node (ref "Q7") (pin "D@3") (pinfunction "D_D@3") (pintype "passive"))
      (node (ref "Q7") (pin "D@4") (pinfunction "D_D@4") (pintype "passive"))
      (node (ref "Q7") (pin "D@5") (pinfunction "D_D@5") (pintype "passive"))
    )
    (net (code "42") (name "Net-(Q3-A)") (class "Default")
      (node (ref "Q3") (pin "P$1") (pinfunction "A_P$1") (pintype "bidirectional"))
      (node (ref "R3") (pin "2") (pinfunction "2_2") (pintype "passive"))
    )
    (net (code "43") (name "Net-(Q3-E)") (class "Default")
      (node (ref "Q3") (pin "P$3") (pinfunction "E_P$3") (pintype "bidirectional"))
      (node (ref "Q8") (pin "D@1") (pinfunction "D_D@1") (pintype "passive"))
      (node (ref "Q8") (pin "D@2") (pinfunction "D_D@2") (pintype "passive"))
      (node (ref "Q8") (pin "D@3") (pinfunction "D_D@3") (pintype "passive"))
      (node (ref "Q8") (pin "D@4") (pinfunction "D_D@4") (pintype "passive"))
      (node (ref "Q8") (pin "D@5") (pinfunction "D_D@5") (pintype "passive"))
    )
    (net (code "44") (name "Net-(Q7-PadG)") (class "Default")
      (node (ref "Q7") (pin "G") (pinfunction "G_G") (pintype "passive"))
      (node (ref "R19") (pin "2") (pinfunction "2_2") (pintype "passive"))
    )
    (net (code "45") (name "Net-(Q7-S-PadS@1)") (class "Default")
      (node (ref "Q7") (pin "S@1") (pinfunction "S_S@1") (pintype "passive"))
      (node (ref "Q7") (pin "S@2") (pinfunction "S_S@2") (pintype "passive"))
      (node (ref "Q7") (pin "S@3") (pinfunction "S_S@3") (pintype "passive"))
      (node (ref "R6") (pin "2") (pinfunction "2_2") (pintype "passive"))
    )
    (net (code "46") (name "Net-(Q8-PadG)") (class "Default")
      (node (ref "Q8") (pin "G") (pinfunction "G_G") (pintype "passive"))
      (node (ref "R20") (pin "2") (pinfunction "2_2") (pintype "passive"))
    )
    (net (code "47") (name "Net-(Q8-S-PadS@1)") (class "Default")
      (node (ref "Q8") (pin "S@1") (pinfunction "S_S@1") (pintype "passive"))
      (node (ref "Q8") (pin "S@2") (pinfunction "S_S@2") (pintype "passive"))
      (node (ref "Q8") (pin "S@3") (pinfunction "S_S@3") (pintype "passive"))
      (node (ref "R7") (pin "2") (pinfunction "2_2") (pintype "passive"))
    )
    (net (code "48") (name "Net-(Q9-PadG)") (class "Default")
      (node (ref "Q9") (pin "G") (pinfunction "G_G") (pintype "passive"))
      (node (ref "R21") (pin "2") (pinfunction "2_2") (pintype "passive"))
    )
    (net (code "49") (name "Net-(Q9-S-PadS@1)") (class "Default")
      (node (ref "Q9") (pin "S@1") (pinfunction "S_S@1") (pintype "passive"))
      (node (ref "Q9") (pin "S@2") (pinfunction "S_S@2") (pintype "passive"))
      (node (ref "Q9") (pin "S@3") (pinfunction "S_S@3") (pintype "passive"))
      (node (ref "R5") (pin "2") (pinfunction "2_2") (pintype "passive"))
    )
    (net (code "50") (name "Net-(U4-RXD)") (class "Default")
      (node (ref "R17") (pin "2") (pinfunction "2_2") (pintype "passive"))
      (node (ref "U4") (pin "4") (pinfunction "RXD_4") (pintype "bidirectional"))
    )
    (net (code "51") (name "Net-(U4-STB)") (class "Default")
      (node (ref "R18") (pin "2") (pinfunction "2_2") (pintype "passive"))
      (node (ref "U4") (pin "8") (pinfunction "STB_8") (pintype "bidirectional"))
    )
    (net (code "52") (name "Net-(U4-TXD)") (class "Default")
      (node (ref "R16") (pin "2") (pinfunction "2_2") (pintype "passive"))
      (node (ref "U4") (pin "1") (pinfunction "TXD_1") (pintype "bidirectional"))
    )
    (net (code "53") (name "Net-(U5-~{VALID1})") (class "Default")
      (node (ref "LED2") (pin "C") (pinfunction "C_C") (pintype "passive"))
      (node (ref "U5") (pin "!VALID1") (pinfunction "~{VALID1}_!VALID1") (pintype "bidirectional"))
    )
    (net (code "54") (name "Net-(U5-~{VALID2})") (class "Default")
      (node (ref "LED1") (pin "C") (pinfunction "C_C") (pintype "passive"))
      (node (ref "U5") (pin "!VALID2") (pinfunction "~{VALID2}_!VALID2") (pintype "bidirectional"))
    )
    (net (code "55") (name "OV1") (class "Default")
      (node (ref "R23") (pin "1") (pinfunction "1_1") (pintype "passive"))
      (node (ref "R24") (pin "2") (pinfunction "2_2") (pintype "passive"))
      (node (ref "U5") (pin "OV1") (pinfunction "OV1_OV1") (pintype "bidirectional"))
    )
    (net (code "56") (name "OV2") (class "Default")
      (node (ref "R26") (pin "1") (pinfunction "1_1") (pintype "passive"))
      (node (ref "R27") (pin "2") (pinfunction "2_2") (pintype "passive"))
      (node (ref "U5") (pin "OV2") (pinfunction "OV2_OV2") (pintype "bidirectional"))
    )
    (net (code "57") (name "PV_OUT") (class "Default")
      (node (ref "U1") (pin "10") (pinfunction "PV_10") (pintype "output"))
      (node (ref "U2") (pin "10") (pinfunction "PV_10") (pintype "output"))
      (node (ref "U3") (pin "7") (pinfunction "7/RX3_7") (pintype "bidirectional"))
    )
    (net (code "58") (name "SCL") (class "Default")
      (node (ref "JP6") (pin "5") (pinfunction "5_5") (pintype "passive"))
      (node (ref "JP6") (pin "6") (pinfunction "6_6") (pintype "passive"))
      (node (ref "R14") (pin "2") (pinfunction "2_2") (pintype "passive"))
      (node (ref "U1") (pin "6") (pinfunction "SCL_6") (pintype "input"))
      (node (ref "U2") (pin "6") (pinfunction "SCL_6") (pintype "input"))
      (node (ref "U3") (pin "19/A5") (pinfunction "19/A5/T/SCL0_19/A5") (pintype "bidirectional"))
    )
    (net (code "59") (name "SDA") (class "Default")
      (node (ref "JP6") (pin "3") (pinfunction "3_3") (pintype "passive"))
      (node (ref "JP6") (pin "4") (pinfunction "4_4") (pintype "passive"))
      (node (ref "R15") (pin "2") (pinfunction "2_2") (pintype "passive"))
      (node (ref "U1") (pin "7") (pinfunction "SDA_7") (pintype "bidirectional"))
      (node (ref "U2") (pin "7") (pinfunction "SDA_7") (pintype "bidirectional"))
      (node (ref "U3") (pin "18/A4") (pinfunction "18/A4/T/SDA0_18/A4") (pintype "bidirectional"))
    )
    (net (code "60") (name "TC_OUT") (class "Default")
      (node (ref "U1") (pin "13") (pinfunction "TC_13") (pintype "output"))
      (node (ref "U2") (pin "13") (pinfunction "TC_13") (pintype "output"))
      (node (ref "U3") (pin "8") (pinfunction "8/TX3_8") (pintype "bidirectional"))
    )
    (net (code "61") (name "UV1") (class "Default")
      (node (ref "R22") (pin "1") (pinfunction "1_1") (pintype "passive"))
      (node (ref "R23") (pin "2") (pinfunction "2_2") (pintype "passive"))
      (node (ref "U5") (pin "UV1") (pinfunction "UV1_UV1") (pintype "bidirectional"))
    )
    (net (code "62") (name "UV2") (class "Default")
      (node (ref "R25") (pin "1") (pinfunction "1_1") (pintype "passive"))
      (node (ref "R26") (pin "2") (pinfunction "2_2") (pintype "passive"))
      (node (ref "U5") (pin "UV2") (pinfunction "UV2_UV2") (pintype "bidirectional"))
    )
    (net (code "63") (name "VIN") (class "Default")
      (node (ref "C4") (pin "1") (pinfunction "1_1") (pintype "passive"))
      (node (ref "JP4") (pin "1") (pinfunction "1_1") (pintype "passive"))
      (node (ref "U3") (pin "VIN") (pinfunction "VIN_VIN") (pintype "power_in"))
      (node (ref "U4") (pin "3") (pinfunction "VCC_3") (pintype "bidirectional"))
    )
    (net (code "64") (name "VS1") (class "Default")
      (node (ref "C9") (pin "1") (pinfunction "1_1") (pintype "passive"))
      (node (ref "Q10") (pin "S@1") (pinfunction "S_S@1") (pintype "passive"))
      (node (ref "Q10") (pin "S@2") (pinfunction "S_S@2") (pintype "passive"))
      (node (ref "Q10") (pin "S@3") (pinfunction "S_S@3") (pintype "passive"))
      (node (ref "Q11") (pin "S@1") (pinfunction "S_S@1") (pintype "passive"))
      (node (ref "Q11") (pin "S@2") (pinfunction "S_S@2") (pintype "passive"))
      (node (ref "Q11") (pin "S@3") (pinfunction "S_S@3") (pintype "passive"))
      (node (ref "U5") (pin "VS1") (pinfunction "VS1_VS1") (pintype "bidirectional"))
    )
    (net (code "65") (name "VS2") (class "Default")
      (node (ref "C10") (pin "1") (pinfunction "1_1") (pintype "passive"))
      (node (ref "Q12") (pin "S@1") (pinfunction "S_S@1") (pintype "passive"))
      (node (ref "Q12") (pin "S@2") (pinfunction "S_S@2") (pintype "passive"))
      (node (ref "Q12") (pin "S@3") (pinfunction "S_S@3") (pintype "passive"))
      (node (ref "Q13") (pin "S@1") (pinfunction "S_S@1") (pintype "passive"))
      (node (ref "Q13") (pin "S@2") (pinfunction "S_S@2") (pintype "passive"))
      (node (ref "Q13") (pin "S@3") (pinfunction "S_S@3") (pintype "passive"))
      (node (ref "U5") (pin "VS2") (pinfunction "VS2_VS2") (pintype "bidirectional"))
    )
    (net (code "66") (name "WALL") (class "Default")
      (node (ref "C7") (pin "1") (pinfunction "1_1") (pintype "passive"))
      (node (ref "J9") (pin "2") (pinfunction "KL1_2") (pintype "passive"))
      (node (ref "Q10") (pin "D@1") (pinfunction "D_D@1") (pintype "passive"))
      (node (ref "Q10") (pin "D@2") (pinfunction "D_D@2") (pintype "passive"))
      (node (ref "Q10") (pin "D@3") (pinfunction "D_D@3") (pintype "passive"))
      (node (ref "Q10") (pin "D@4") (pinfunction "D_D@4") (pintype "passive"))
      (node (ref "Q10") (pin "D@5") (pinfunction "D_D@5") (pintype "passive"))
      (node (ref "R22") (pin "2") (pinfunction "2_2") (pintype "passive"))
      (node (ref "U5") (pin "V1") (pinfunction "V1_V1") (pintype "bidirectional"))
    )
    (net (code "67") (name "WARNING_OUT") (class "Default")
      (node (ref "U1") (pin "8") (pinfunction "WARNING_8") (pintype "output"))
      (node (ref "U2") (pin "8") (pinfunction "WARNING_8") (pintype "output"))
      (node (ref "U3") (pin "10") (pinfunction "10/TX2/PWM_10") (pintype "bidirectional"))
    )
    (net (code "68") (name "unconnected-(U1-IN+3-Pad2)") (class "Default")
      (node (ref "U1") (pin "2") (pinfunction "IN+3_2") (pintype "input"))
    )
    (net (code "69") (name "unconnected-(U2-IN+3-Pad2)") (class "Default")
      (node (ref "U2") (pin "2") (pinfunction "IN+3_2") (pintype "input"))
    )
    (net (code "70") (name "unconnected-(U3-0{slash}RX1{slash}T-Pad0)") (class "Default")
      (node (ref "U3") (pin "0") (pinfunction "0/RX1/T_0") (pintype "bidirectional"))
    )
    (net (code "71") (name "unconnected-(U3-1{slash}TX1{slash}T-Pad1)") (class "Default")
      (node (ref "U3") (pin "1") (pinfunction "1/TX1/T_1") (pintype "bidirectional"))
    )
    (net (code "72") (name "unconnected-(U3-5{slash}PWM-Pad5)") (class "Default")
      (node (ref "U3") (pin "5") (pinfunction "5/PWM_5") (pintype "bidirectional"))
    )
    (net (code "73") (name "unconnected-(U3-6{slash}PWM-Pad6)") (class "Default")
      (node (ref "U3") (pin "6") (pinfunction "6/PWM_6") (pintype "bidirectional"))
    )
    (net (code "74") (name "unconnected-(U3-11{slash}MOSI-Pad11)") (class "Default")
      (node (ref "U3") (pin "11") (pinfunction "11/MOSI_11") (pintype "bidirectional"))
    )
    (net (code "75") (name "unconnected-(U3-12{slash}MISO-Pad12)") (class "Default")
      (node (ref "U3") (pin "12") (pinfunction "12/MISO_12") (pintype "bidirectional"))
    )
    (net (code "76") (name "unconnected-(U3-13{slash}SCK{slash}LED-Pad13)") (class "Default")
      (node (ref "U3") (pin "13") (pinfunction "13/SCK/LED_13") (pintype "bidirectional"))
    )
    (net (code "77") (name "unconnected-(U3-15{slash}A1{slash}T-Pad15{slash}A1)") (class "Default")
      (node (ref "U3") (pin "15/A1") (pinfunction "15/A1/T_15/A1") (pintype "bidirectional"))
    )
    (net (code "78") (name "unconnected-(U3-16{slash}A2{slash}T-Pad16{slash}A2)") (class "Default")
      (node (ref "U3") (pin "16/A2") (pinfunction "16/A2/T_16/A2") (pintype "bidirectional"))
    )
    (net (code "79") (name "unconnected-(U3-17{slash}A3{slash}T-Pad17{slash}A3)") (class "Default")
      (node (ref "U3") (pin "17/A3") (pinfunction "17/A3/T_17/A3") (pintype "bidirectional"))
    )
    (net (code "80") (name "unconnected-(U3-20{slash}A6{slash}PWM-Pad20{slash}A6)") (class "Default")
      (node (ref "U3") (pin "20/A6") (pinfunction "20/A6/PWM_20/A6") (pintype "bidirectional"))
    )
    (net (code "81") (name "unconnected-(U3-21{slash}A7{slash}PWM-Pad21{slash}A7)") (class "Default")
      (node (ref "U3") (pin "21/A7") (pinfunction "21/A7/PWM_21/A7") (pintype "bidirectional"))
    )
    (net (code "82") (name "unconnected-(U3-22{slash}A8{slash}T{slash}PWM-Pad22{slash}A8)") (class "Default")
      (node (ref "U3") (pin "22/A8") (pinfunction "22/A8/T/PWM_22/A8") (pintype "bidirectional"))
    )
    (net (code "83") (name "unconnected-(U3-23{slash}A9{slash}T{slash}PWM-Pad23{slash}A9)") (class "Default")
      (node (ref "U3") (pin "23/A9") (pinfunction "23/A9/T/PWM_23/A9") (pintype "bidirectional"))
    )
    (net (code "84") (name "unconnected-(U3-Pad2)") (class "Default")
      (node (ref "U3") (pin "2") (pinfunction "2_2") (pintype "bidirectional"))
    )
    (net (code "85") (name "unconnected-(U3-Pad14{slash}A0)") (class "Default")
      (node (ref "U3") (pin "14/A0") (pinfunction "14/A0_14/A0") (pintype "bidirectional"))
    )
    (net (code "86") (name "unconnected-(U5-PadCAS)") (class "Default")
      (node (ref "U5") (pin "CAS") (pinfunction "CAS_CAS") (pintype "bidirectional"))
    )
  )
)
